# Simple_Regulated_Bench_Power_Supply.net
KiCad netlist of a schematic drawn in EasyEDA Pro
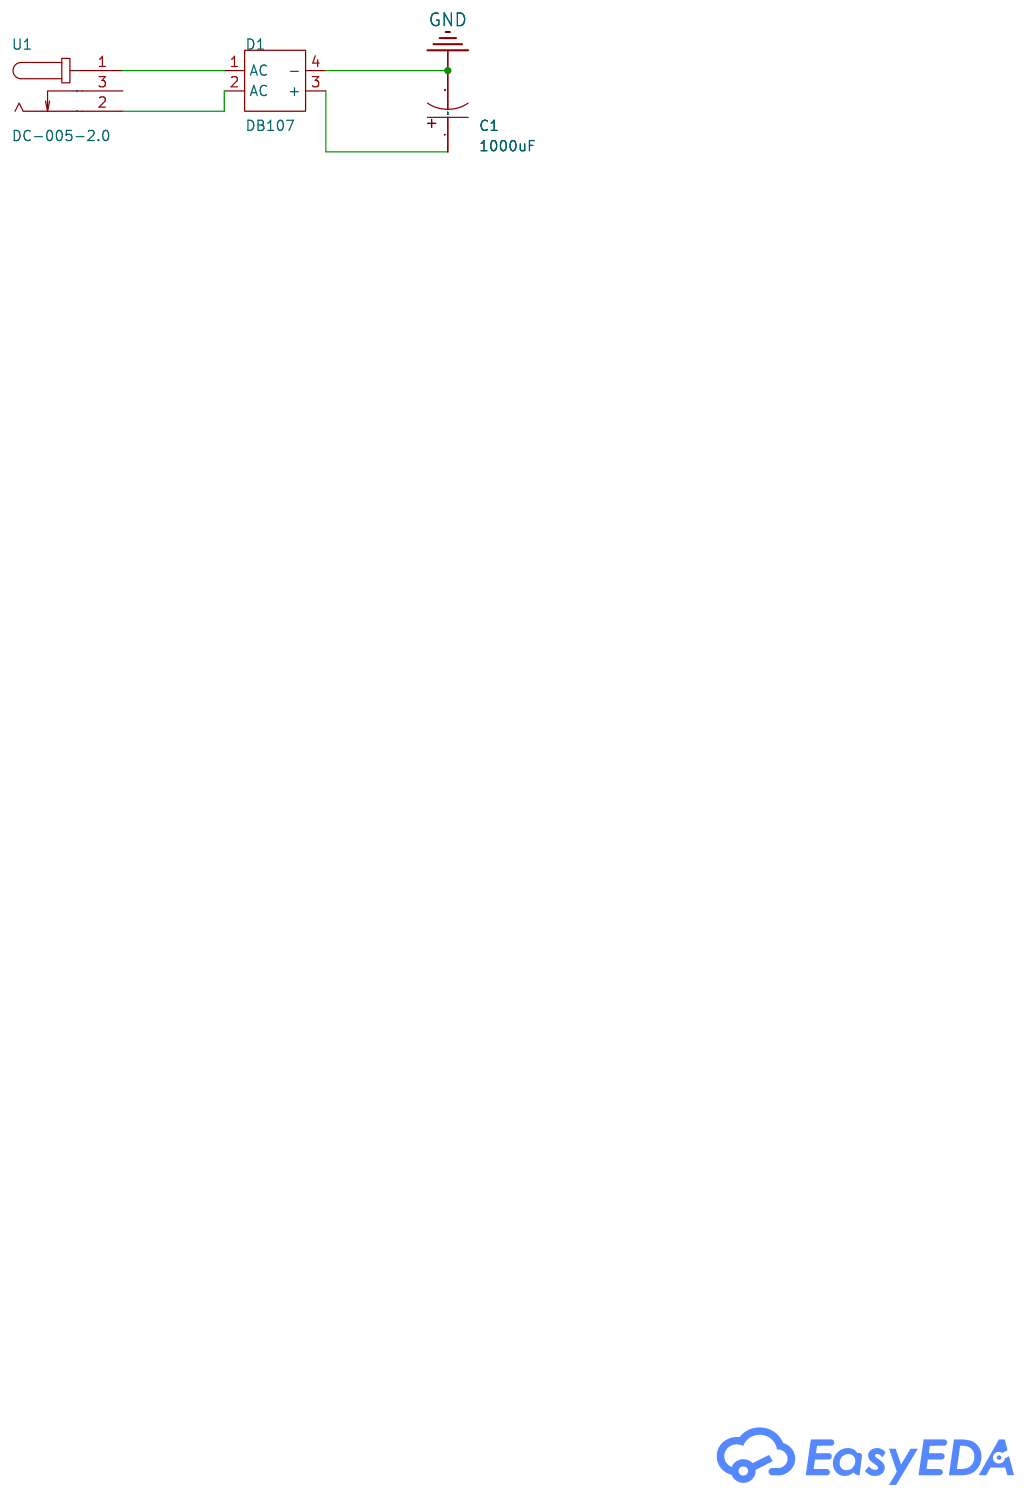
[diagram p0: schematic sheet]

(export (version "E")
  (design (tool "Eeschema 10.0.6"))
  (components
    (comp (ref "C1")
      (value "1000uF")
      (footprint "easyedapro:CAP-TH_BD10.0-P5.00-D1.0-FD")
      (fields (field (name "Manufacturer Part") "ERR1VM102G20OT") (field (name "Manufacturer") "AISHI(艾华集团)"))
      (libsource (lib "easyedapro") (part "ERR1VM102G20OT"))
    )
    (comp (ref "D1")
      (value "DB107")
      (footprint "easyedapro:DIO-BG-TH_DB107")
      (fields (field (name "Manufacturer") "TOS(熙隆半导体)"))
      (libsource (lib "easyedapro") (part "DB107_C52750554"))
    )
    (comp (ref "U1")
      (value "DC-005-2.0")
      (footprint "easyedapro:DC-IN-TH_DC-005-2.0_C22459640")
      (fields (field (name "Manufacturer") "HanElectricity(瀚源)"))
      (libsource (lib "easyedapro") (part "DC-005-2.0_C22459640"))
    )
  )
  (nets
    (net (code "1") (name "GND") (class "Default")
      (node (ref "C1") (pin "2") (pinfunction "2_2") (pintype "unspecified"))
      (node (ref "D1") (pin "4") (pinfunction "-_4") (pintype "unspecified"))
    )
    (net (code "2") (name "Net-(D1-+)") (class "Default")
      (node (ref "C1") (pin "1") (pinfunction "1_1") (pintype "unspecified"))
      (node (ref "D1") (pin "3") (pinfunction "+_3") (pintype "unspecified"))
    )
    (net (code "3") (name "Net-(D1-AC-Pad1)") (class "Default")
      (node (ref "D1") (pin "1") (pinfunction "AC_1") (pintype "unspecified"))
      (node (ref "U1") (pin "1") (pinfunction "1_1") (pintype "unspecified"))
    )
    (net (code "4") (name "Net-(D1-AC-Pad2)") (class "Default")
      (node (ref "D1") (pin "2") (pinfunction "AC_2") (pintype "unspecified"))
      (node (ref "U1") (pin "2") (pinfunction "2_2") (pintype "unspecified"))
    )
    (net (code "5") (name "unconnected-(U1-Pad3)") (class "Default")
      (node (ref "U1") (pin "3") (pinfunction "3_3") (pintype "unspecified"))
    )
  )
)
